# Power_Test.net
KiCad netlist of a schematic drawn in EasyEDA Pro
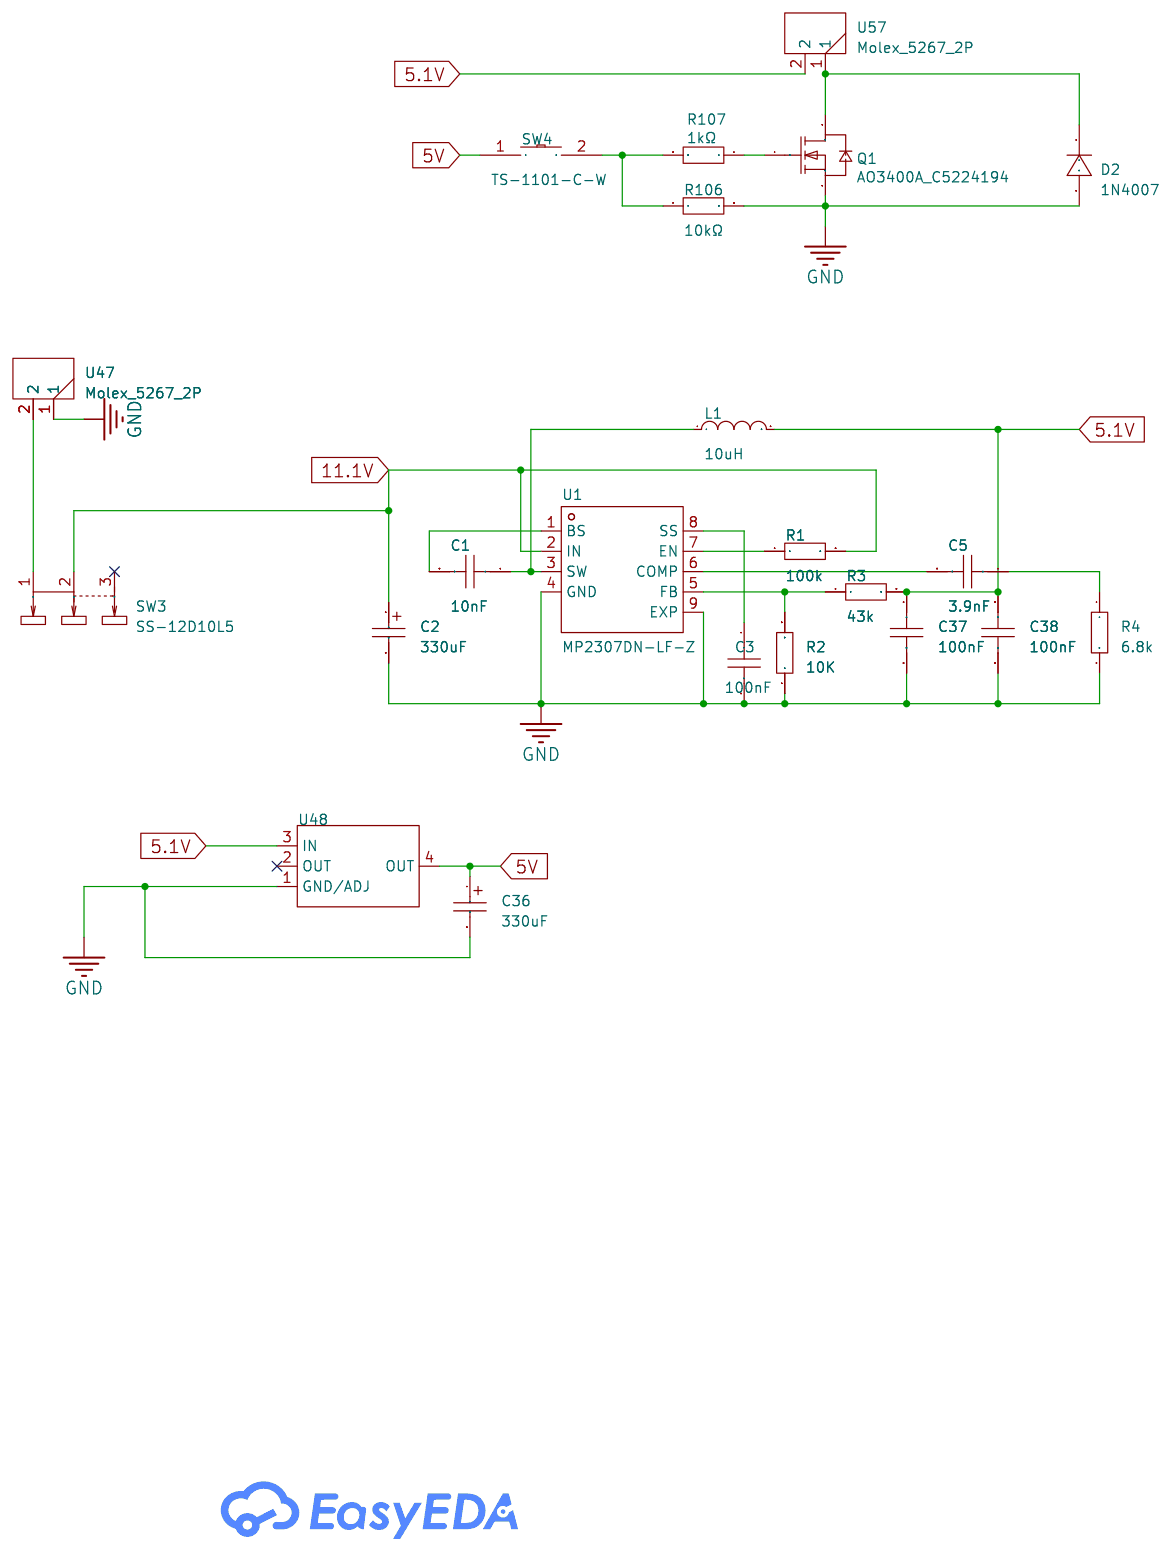
[diagram p0: schematic sheet]

(export (version "E")
  (design (tool "Eeschema 10.0.6"))
  (components
    (comp (ref "C1")
      (value "10nF")
      (footprint "easyedapro:C0603")
      (libsource (lib "easyedapro") (part "CAP"))
    )
    (comp (ref "C2")
      (value "330uF")
      (footprint "easyedapro:CASE-D_7343")
      (fields (field (name "Manufacturer Part") "TAJD337K010RNJ") (field (name "Manufacturer") "Kyocera AVX"))
      (libsource (lib "easyedapro") (part "TAJD337K010RNJ"))
    )
    (comp (ref "C3")
      (value "100nF")
      (footprint "easyedapro:C0603")
      (libsource (lib "easyedapro") (part "CAP"))
    )
    (comp (ref "C5")
      (value "3.9nF")
      (footprint "easyedapro:C0603")
      (libsource (lib "easyedapro") (part "CAP"))
    )
    (comp (ref "C36")
      (value "330uF")
      (footprint "easyedapro:CASE-D_7343")
      (fields (field (name "Manufacturer Part") "TAJD337K010RNJ") (field (name "Manufacturer") "Kyocera AVX"))
      (libsource (lib "easyedapro") (part "TAJD337K010RNJ"))
    )
    (comp (ref "C37")
      (value "100nF")
      (footprint "easyedapro:C0603")
      (libsource (lib "easyedapro") (part "CAP"))
    )
    (comp (ref "C38")
      (value "100nF")
      (footprint "easyedapro:C0603")
      (libsource (lib "easyedapro") (part "CAP"))
    )
    (comp (ref "D2")
      (value "1N4007")
      (footprint "easyedapro:SMA_L4.4-W2.8-LS5.4-RD")
      (fields (field (name "Manufacturer") "SHIKUES(时科)"))
      (libsource (lib "easyedapro") (part "1N4007_C126233"))
    )
    (comp (ref "L1")
      (value "10uH")
      (footprint "easyedapro:IND-SMD_L7.3-W6.6")
      (fields
        (field (name "Manufacturer Part") "BMRB00060630100MA1")
        (field (name "Manufacturer") "Chilisin(奇力新)")
      )
      (libsource (lib "easyedapro") (part "BMRB00060630100MA1"))
    )
    (comp (ref "Q1")
      (value "AO3400A_C5224194")
      (footprint "easyedapro:SOT-23-3_L3.0-W1.6-P1.90-LS2.8-BR")
      (fields (field (name "Manufacturer Part") "AO3400A") (field (name "Manufacturer") "ElecSuper(静芯微)"))
      (libsource (lib "easyedapro") (part "AO3400A_C5224194"))
    )
    (comp (ref "R1")
      (value "100k")
      (footprint "easyedapro:R0603")
      (libsource (lib "easyedapro") (part "Res"))
    )
    (comp (ref "R2") (value "10K") (footprint "easyedapro:R0603") (libsource (lib "easyedapro") (part "Res")))
    (comp (ref "R3") (value "43k") (footprint "easyedapro:R0603") (libsource (lib "easyedapro") (part "Res")))
    (comp (ref "R4")
      (value "6.8k")
      (footprint "easyedapro:R0603")
      (libsource (lib "easyedapro") (part "Res"))
    )
    (comp (ref "R106")
      (value "10kΩ")
      (footprint "easyedapro:R0603")
      (fields
        (field (name "Manufacturer Part") "0603WAF1001T5E")
        (field (name "Manufacturer") "UNI-ROYAL(厚声)")
      )
      (libsource (lib "easyedapro") (part "1kΩ"))
    )
    (comp (ref "R107")
      (value "1kΩ")
      (footprint "easyedapro:R0603")
      (fields
        (field (name "Manufacturer Part") "0603WAF1001T5E")
        (field (name "Manufacturer") "UNI-ROYAL(厚声)")
      )
      (libsource (lib "easyedapro") (part "1kΩ"))
    )
    (comp (ref "SW3")
      (value "SS-12D10L5")
      (footprint "easyedapro:SW-TH_SS-12D10L5")
      (fields (field (name "Manufacturer") "XKB Connectivity(中国星坤)"))
      (libsource (lib "easyedapro") (part "SS-12D10L5"))
    )
    (comp (ref "SW4")
      (value "TS-1101-C-W")
      (footprint "easyedapro:SW-SMD_L6.0-W3.3-LS8.0")
      (fields (field (name "Manufacturer") "XKB Connectivity(中国星坤)"))
      (libsource (lib "easyedapro") (part "TS-1101-C-W"))
    )
    (comp (ref "U1")
      (value "MP2307DN-LF-Z")
      (footprint "easyedapro:SOP-8_L4.9-W3.9-P1.27-LS6.0-BL-EP")
      (fields (field (name "Manufacturer") "MPS(芯源)"))
      (libsource (lib "easyedapro") (part "MP2307DN-LF-Z"))
    )
    (comp (ref "U47")
      (value "Molex_5267_2P")
      (footprint "easyedapro:5267_2P")
      (libsource (lib "easyedapro") (part "Molex_5267_2P"))
    )
    (comp (ref "U48")
      (value "AMS1117-5.0")
      (footprint "easyedapro:SOT-223-4_L6.5-W3.5-P2.30-LS7.0-BR")
      (fields (field (name "Manufacturer") "KEXIN(科信)"))
      (libsource (lib "easyedapro") (part "AMS1117-5.0_C489390"))
    )
    (comp (ref "U57")
      (value "Molex_5267_2P")
      (footprint "easyedapro:5267_2P")
      (libsource (lib "easyedapro") (part "Molex_5267_2P"))
    )
  )
  (nets
    (net (code "1") (name "5.1V") (class "Default")
      (node (ref "C37") (pin "1") (pinfunction "1_1") (pintype "input"))
      (node (ref "C38") (pin "1") (pinfunction "1_1") (pintype "input"))
      (node (ref "L1") (pin "2") (pinfunction "2_2") (pintype "unspecified"))
      (node (ref "R3") (pin "2") (pinfunction "2_2") (pintype "input"))
      (node (ref "U48") (pin "3") (pinfunction "IN_3") (pintype "unspecified"))
      (node (ref "U57") (pin "2") (pinfunction "2_2") (pintype "unspecified"))
    )
    (net (code "2") (name "5V") (class "Default")
      (node (ref "C36") (pin "1") (pinfunction "1_1") (pintype "input"))
      (node (ref "SW4") (pin "1") (pinfunction "1_1") (pintype "unspecified"))
      (node (ref "U48") (pin "4") (pinfunction "OUT_4") (pintype "unspecified"))
    )
    (net (code "3") (name "11.1V") (class "Default")
      (node (ref "C2") (pin "1") (pinfunction "1_1") (pintype "input"))
      (node (ref "R1") (pin "2") (pinfunction "2_2") (pintype "input"))
      (node (ref "SW3") (pin "2") (pinfunction "2_2") (pintype "unspecified"))
      (node (ref "U1") (pin "2") (pinfunction "IN_2") (pintype "unspecified"))
    )
    (net (code "4") (name "GND") (class "Default")
      (node (ref "C2") (pin "2") (pinfunction "2_2") (pintype "input"))
      (node (ref "C3") (pin "2") (pinfunction "2_2") (pintype "input"))
      (node (ref "C36") (pin "2") (pinfunction "2_2") (pintype "input"))
      (node (ref "C37") (pin "2") (pinfunction "2_2") (pintype "input"))
      (node (ref "C38") (pin "2") (pinfunction "2_2") (pintype "input"))
      (node (ref "D2") (pin "2") (pinfunction "2_2") (pintype "unspecified"))
      (node (ref "Q1") (pin "2") (pinfunction "S_2") (pintype "unspecified"))
      (node (ref "R106") (pin "2") (pinfunction "2_2") (pintype "input"))
      (node (ref "R2") (pin "1") (pinfunction "1_1") (pintype "input"))
      (node (ref "R4") (pin "2") (pinfunction "2_2") (pintype "input"))
      (node (ref "U1") (pin "4") (pinfunction "GND_4") (pintype "unspecified"))
      (node (ref "U1") (pin "9") (pinfunction "EXP_9") (pintype "unspecified"))
      (node (ref "U47") (pin "1") (pinfunction "1_1") (pintype "unspecified"))
      (node (ref "U48") (pin "1") (pinfunction "GND/ADJ_1") (pintype "unspecified"))
    )
    (net (code "5") (name "Net-(C5-Pad1)") (class "Default")
      (node (ref "C5") (pin "1") (pinfunction "1_1") (pintype "input"))
      (node (ref "R4") (pin "1") (pinfunction "1_1") (pintype "input"))
    )
    (net (code "6") (name "Net-(Q1-D)") (class "Default")
      (node (ref "D2") (pin "1") (pinfunction "1_1") (pintype "unspecified"))
      (node (ref "Q1") (pin "3") (pinfunction "D_3") (pintype "unspecified"))
      (node (ref "U57") (pin "1") (pinfunction "1_1") (pintype "unspecified"))
    )
    (net (code "7") (name "Net-(Q1-G)") (class "Default")
      (node (ref "Q1") (pin "1") (pinfunction "G_1") (pintype "unspecified"))
      (node (ref "R107") (pin "1") (pinfunction "1_1") (pintype "input"))
    )
    (net (code "8") (name "Net-(R106-Pad1)") (class "Default")
      (node (ref "R106") (pin "1") (pinfunction "1_1") (pintype "input"))
      (node (ref "R107") (pin "2") (pinfunction "2_2") (pintype "input"))
      (node (ref "SW4") (pin "2") (pinfunction "2_2") (pintype "unspecified"))
    )
    (net (code "9") (name "Net-(SW3-Pad1)") (class "Default")
      (node (ref "SW3") (pin "1") (pinfunction "1_1") (pintype "unspecified"))
      (node (ref "U47") (pin "2") (pinfunction "2_2") (pintype "unspecified"))
    )
    (net (code "10") (name "Net-(U1-BS)") (class "Default")
      (node (ref "C1") (pin "2") (pinfunction "2_2") (pintype "input"))
      (node (ref "U1") (pin "1") (pinfunction "BS_1") (pintype "unspecified"))
    )
    (net (code "11") (name "Net-(U1-COMP)") (class "Default")
      (node (ref "C5") (pin "2") (pinfunction "2_2") (pintype "input"))
      (node (ref "U1") (pin "6") (pinfunction "COMP_6") (pintype "unspecified"))
    )
    (net (code "12") (name "Net-(U1-EN)") (class "Default")
      (node (ref "R1") (pin "1") (pinfunction "1_1") (pintype "input"))
      (node (ref "U1") (pin "7") (pinfunction "EN_7") (pintype "unspecified"))
    )
    (net (code "13") (name "Net-(U1-FB)") (class "Default")
      (node (ref "R2") (pin "2") (pinfunction "2_2") (pintype "input"))
      (node (ref "R3") (pin "1") (pinfunction "1_1") (pintype "input"))
      (node (ref "U1") (pin "5") (pinfunction "FB_5") (pintype "unspecified"))
    )
    (net (code "14") (name "Net-(U1-SS)") (class "Default")
      (node (ref "C3") (pin "1") (pinfunction "1_1") (pintype "input"))
      (node (ref "U1") (pin "8") (pinfunction "SS_8") (pintype "unspecified"))
    )
    (net (code "15") (name "Net-(U1-SW)") (class "Default")
      (node (ref "C1") (pin "1") (pinfunction "1_1") (pintype "input"))
      (node (ref "L1") (pin "1") (pinfunction "1_1") (pintype "unspecified"))
      (node (ref "U1") (pin "3") (pinfunction "SW_3") (pintype "unspecified"))
    )
    (net (code "16") (name "unconnected-(SW3-Pad3)") (class "Default")
      (node (ref "SW3") (pin "3") (pinfunction "3_3") (pintype "unspecified+no_connect"))
    )
    (net (code "17") (name "unconnected-(U48-OUT-Pad2)") (class "Default")
      (node (ref "U48") (pin "2") (pinfunction "OUT_2") (pintype "unspecified+no_connect"))
    )
  )
)
